# kalicki3v3.net
KiCad netlist of a schematic drawn in EAGLE
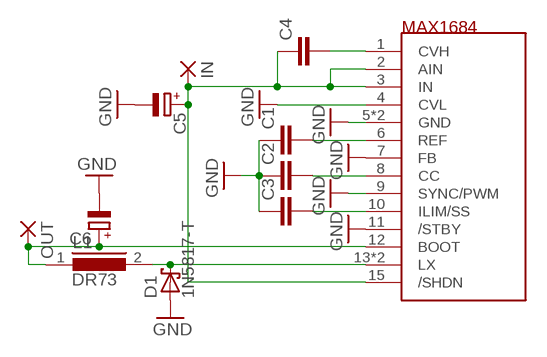
[diagram p0: schematic, sheet 1]

(export (version "E")
  (design (tool "Eeschema 10.0.6"))
  (components
    (comp (ref "C1")
      (value "C-EUC0805")
      (footprint "eagle-import:C0805")
      (libsource (lib "eagle-import") (part "C-EUC0805"))
    )
    (comp (ref "C2")
      (value "C-EUC0805")
      (footprint "eagle-import:C0805")
      (libsource (lib "eagle-import") (part "C-EUC0805"))
    )
    (comp (ref "C3")
      (value "C-EUC0805")
      (footprint "eagle-import:C0805")
      (libsource (lib "eagle-import") (part "C-EUC0805"))
    )
    (comp (ref "C4")
      (value "C-EUC0805")
      (footprint "eagle-import:C0805")
      (libsource (lib "eagle-import") (part "C-EUC0805"))
    )
    (comp (ref "C5")
      (value "CPOL-EUE2.5-7")
      (footprint "eagle-import:E2,5-7")
      (libsource (lib "eagle-import") (part "CPOL-EUE2.5-7"))
    )
    (comp (ref "C6")
      (value "CPOL-EUE2.5-7")
      (footprint "eagle-import:E2,5-7")
      (libsource (lib "eagle-import") (part "CPOL-EUE2.5-7"))
    )
    (comp (ref "D1")
      (value "1N5817-T")
      (footprint "eagle-import:DO41-7.6")
      (libsource (lib "eagle-import") (part "1N5817-T"))
    )
    (comp (ref "IN")
      (value "2,54/0,8")
      (footprint "eagle-import:2,54_0,8")
      (libsource (lib "eagle-import") (part "2,54/0,8"))
    )
    (comp (ref "L1")
      (value "DR73")
      (footprint "eagle-import:DR73")
      (libsource (lib "eagle-import") (part "DR73"))
    )
    (comp (ref "OUT")
      (value "2,54/0,8")
      (footprint "eagle-import:2,54_0,8")
      (libsource (lib "eagle-import") (part "2,54/0,8"))
    )
    (comp (ref "U$1")
      (value "MAX1684")
      (footprint "eagle-import:QSOP16")
      (libsource (lib "eagle-import") (part "MAX1684"))
    )
  )
  (nets
    (net (code "1") (name "GND") (class "Default")
      (node (ref "C1") (pin "1") (pinfunction "1_1") (pintype "passive"))
      (node (ref "C2") (pin "1") (pinfunction "1_1") (pintype "passive"))
      (node (ref "C3") (pin "1") (pinfunction "1_1") (pintype "passive"))
      (node (ref "C5") (pin "-") (pinfunction "-_-") (pintype "passive"))
      (node (ref "C6") (pin "-") (pinfunction "-_-") (pintype "passive"))
      (node (ref "D1") (pin "A") (pinfunction "A_A") (pintype "passive"))
      (node (ref "U$1") (pin "11") (pinfunction "/STBY_11") (pintype "bidirectional"))
      (node (ref "U$1") (pin "16") (pinfunction "GND_16") (pintype "bidirectional"))
      (node (ref "U$1") (pin "4") (pinfunction "CVL_4") (pintype "bidirectional"))
      (node (ref "U$1") (pin "5") (pinfunction "GND_5") (pintype "bidirectional"))
      (node (ref "U$1") (pin "7") (pinfunction "FB_7") (pintype "bidirectional"))
      (node (ref "U$1") (pin "9") (pinfunction "SYNC/PWM_9") (pintype "bidirectional"))
    )
    (net (code "2") (name "Net-(D1-PadC)") (class "Default")
      (node (ref "D1") (pin "C") (pinfunction "C_C") (pintype "passive"))
      (node (ref "L1") (pin "2") (pinfunction "2_2") (pintype "passive"))
      (node (ref "U$1") (pin "13") (pinfunction "LX_13") (pintype "bidirectional"))
      (node (ref "U$1") (pin "14") (pinfunction "LX_14") (pintype "bidirectional"))
    )
    (net (code "3") (name "Net-(IN-P)") (class "Default")
      (node (ref "C4") (pin "1") (pinfunction "1_1") (pintype "passive"))
      (node (ref "C5") (pin "+") (pinfunction "+_+") (pintype "passive"))
      (node (ref "IN") (pin "1") (pinfunction "P_1") (pintype "passive"))
      (node (ref "U$1") (pin "15") (pinfunction "/SHDN_15") (pintype "bidirectional"))
      (node (ref "U$1") (pin "2") (pinfunction "AIN_2") (pintype "bidirectional"))
      (node (ref "U$1") (pin "3") (pinfunction "IN_3") (pintype "bidirectional"))
    )
    (net (code "4") (name "Net-(OUT-P)") (class "Default")
      (node (ref "C6") (pin "+") (pinfunction "+_+") (pintype "passive"))
      (node (ref "L1") (pin "1") (pinfunction "1_1") (pintype "passive"))
      (node (ref "OUT") (pin "1") (pinfunction "P_1") (pintype "passive"))
      (node (ref "U$1") (pin "12") (pinfunction "BOOT_12") (pintype "bidirectional"))
    )
    (net (code "5") (name "Net-(U$1-CC)") (class "Default")
      (node (ref "C2") (pin "2") (pinfunction "2_2") (pintype "passive"))
      (node (ref "U$1") (pin "8") (pinfunction "CC_8") (pintype "bidirectional"))
    )
    (net (code "6") (name "Net-(U$1-CVH)") (class "Default")
      (node (ref "C4") (pin "2") (pinfunction "2_2") (pintype "passive"))
      (node (ref "U$1") (pin "1") (pinfunction "CVH_1") (pintype "bidirectional"))
    )
    (net (code "7") (name "Net-(U$1-ILIM{slash}SS)") (class "Default")
      (node (ref "C3") (pin "2") (pinfunction "2_2") (pintype "passive"))
      (node (ref "U$1") (pin "10") (pinfunction "ILIM/SS_10") (pintype "bidirectional"))
    )
    (net (code "8") (name "Net-(U$1-REF)") (class "Default")
      (node (ref "C1") (pin "2") (pinfunction "2_2") (pintype "passive"))
      (node (ref "U$1") (pin "6") (pinfunction "REF_6") (pintype "bidirectional"))
    )
  )
)
